# clapclap1386.net
KiCad netlist of a schematic drawn in EAGLE
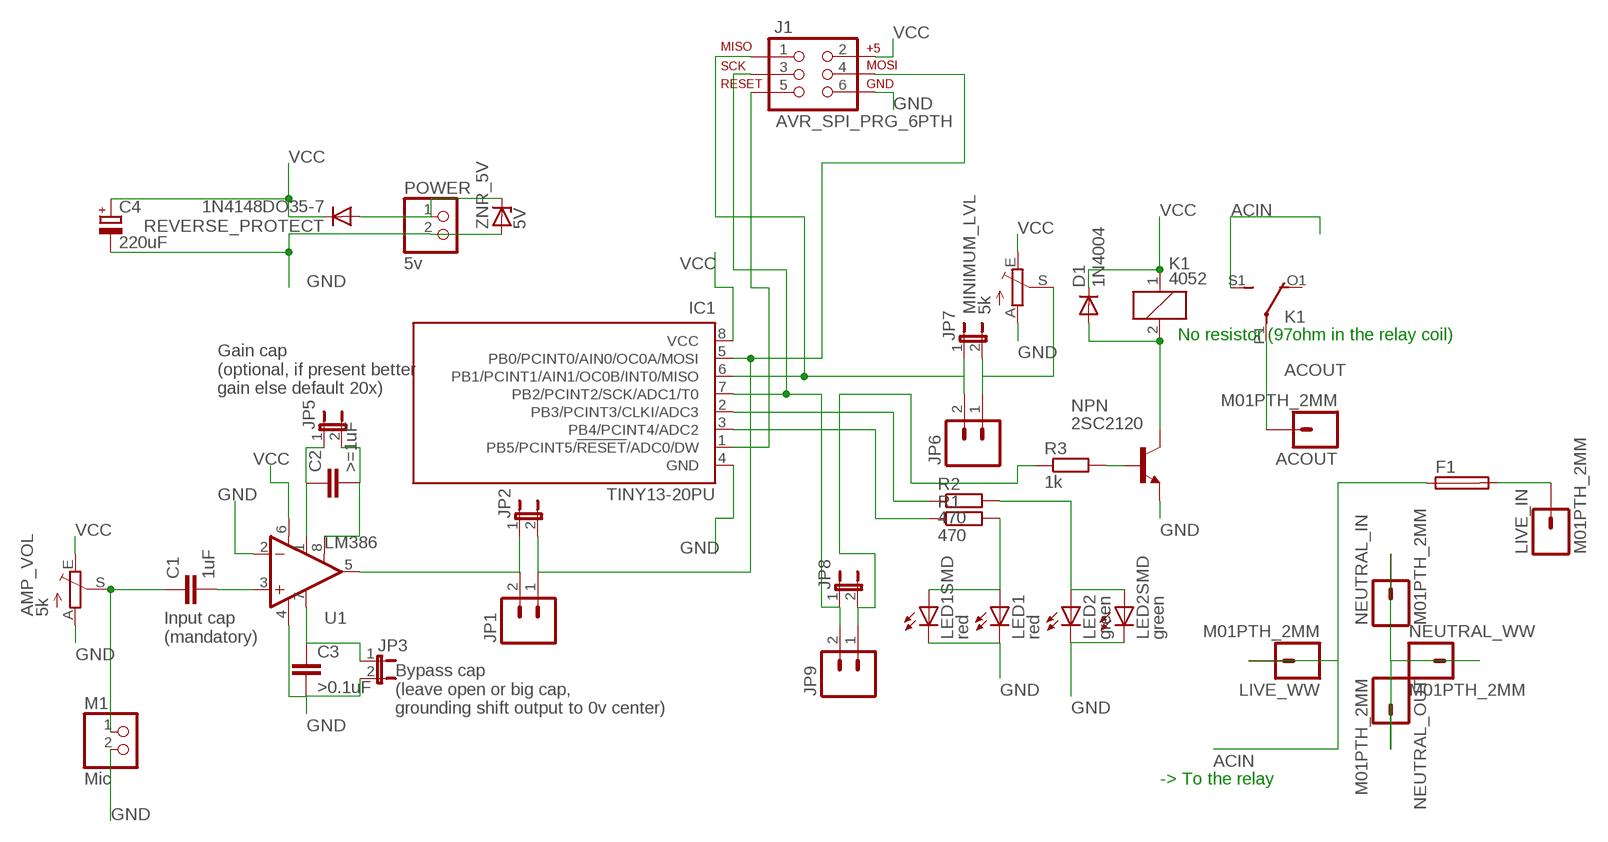
[diagram p0: schematic, sheet 1]

(export (version "E")
  (design (tool "Eeschema 10.0.6"))
  (components
    (comp (ref "ACOUT")
      (value "M01PTH_2MM")
      (footprint "eagle-import:1X01_2MM")
      (libsource (lib "eagle-import") (part "M01PTH_2MM"))
    )
    (comp (ref "AMP_VOL")
      (value "5k")
      (footprint "eagle-import:CT6")
      (libsource (lib "eagle-import") (part "TRIM_EU-CT6"))
    )
    (comp (ref "C1")
      (value "1uF")
      (footprint "eagle-import:C050-024X044")
      (libsource (lib "eagle-import") (part "C-EU050-024X044"))
    )
    (comp (ref "C2")
      (value ">=1uF")
      (footprint "eagle-import:C050-024X044")
      (libsource (lib "eagle-import") (part "C-EU050-024X044"))
    )
    (comp (ref "C3")
      (value ">0.1uF")
      (footprint "eagle-import:C025-025X050")
      (libsource (lib "eagle-import") (part "C-EU025-025X050"))
    )
    (comp (ref "C4")
      (value "220uF")
      (footprint "eagle-import:E2,5-6E")
      (libsource (lib "eagle-import") (part "CPOL-EUE2,5-6E"))
    )
    (comp (ref "D1")
      (value "1N4004")
      (footprint "eagle-import:DO41-10")
      (libsource (lib "eagle-import") (part "1N4004"))
    )
    (comp (ref "F1")
      (value "TE5")
      (footprint "eagle-import:TE5")
      (libsource (lib "eagle-import") (part "TE5"))
    )
    (comp (ref "IC1")
      (value "TINY13-20PU")
      (footprint "eagle-import:DIL08")
      (fields (field (name "MPN") "ATTINY13-20PU"))
      (libsource (lib "eagle-import") (part "TINY13PU-20"))
    )
    (comp (ref "J1")
      (value "AVR_SPI_PRG_6PTH")
      (footprint "eagle-import:2X3")
      (libsource (lib "eagle-import") (part "AVR_SPI_PRG_6PTH"))
    )
    (comp (ref "JP1")
      (value "M02PTH")
      (footprint "eagle-import:1X02")
      (libsource (lib "eagle-import") (part "M02PTH"))
    )
    (comp (ref "JP2")
      (value "JUMPER-2SMD-NO")
      (footprint "eagle-import:SJ_2S-NO")
      (libsource (lib "eagle-import") (part "JUMPER-2SMD-NO"))
    )
    (comp (ref "JP3")
      (value "JUMPER-2SMD-NO")
      (footprint "eagle-import:SJ_2S-NO")
      (libsource (lib "eagle-import") (part "JUMPER-2SMD-NO"))
    )
    (comp (ref "JP5")
      (value "JUMPER-2SMD-NO")
      (footprint "eagle-import:SJ_2S-NO")
      (libsource (lib "eagle-import") (part "JUMPER-2SMD-NO"))
    )
    (comp (ref "JP6")
      (value "M02PTH")
      (footprint "eagle-import:1X02")
      (libsource (lib "eagle-import") (part "M02PTH"))
    )
    (comp (ref "JP7")
      (value "JUMPER-2SMD-NO")
      (footprint "eagle-import:SJ_2S-NO")
      (libsource (lib "eagle-import") (part "JUMPER-2SMD-NO"))
    )
    (comp (ref "JP8")
      (value "JUMPER-2SMD-NO")
      (footprint "eagle-import:SJ_2S-NO")
      (libsource (lib "eagle-import") (part "JUMPER-2SMD-NO"))
    )
    (comp (ref "JP9")
      (value "M02PTH")
      (footprint "eagle-import:1X02")
      (libsource (lib "eagle-import") (part "M02PTH"))
    )
    (comp (ref "K1")
      (value "4052")
      (footprint "eagle-import:F4052")
      (libsource (lib "eagle-import") (part "4052"))
    )
    (comp (ref "LED1")
      (value "red")
      (footprint "eagle-import:LED3MM")
      (libsource (lib "eagle-import") (part "LED3MM"))
    )
    (comp (ref "LED1SMD")
      (value "red")
      (footprint "eagle-import:KA-3528ASYC")
      (libsource (lib "eagle-import") (part "LEDKA-3528ASYC"))
    )
    (comp (ref "LED2")
      (value "green")
      (footprint "eagle-import:LED3MM")
      (libsource (lib "eagle-import") (part "LED3MM"))
    )
    (comp (ref "LED2SMD")
      (value "green")
      (footprint "eagle-import:KA-3528ASYC")
      (libsource (lib "eagle-import") (part "LEDKA-3528ASYC"))
    )
    (comp (ref "LIVE_IN")
      (value "M01PTH_2MM")
      (footprint "eagle-import:1X01_2MM")
      (libsource (lib "eagle-import") (part "M01PTH_2MM"))
    )
    (comp (ref "LIVE_WW")
      (value "M01PTH_2MM")
      (footprint "eagle-import:1X01_2MM")
      (libsource (lib "eagle-import") (part "M01PTH_2MM"))
    )
    (comp (ref "M1")
      (value "Mic")
      (footprint "eagle-import:1X02")
      (libsource (lib "eagle-import") (part "PINHD-1X2"))
    )
    (comp (ref "MINIMUM_LVL")
      (value "5k")
      (footprint "eagle-import:CT6")
      (libsource (lib "eagle-import") (part "TRIM_EU-CT6"))
    )
    (comp (ref "NEUTRAL_IN")
      (value "M01PTH_2MM")
      (footprint "eagle-import:1X01_2MM")
      (libsource (lib "eagle-import") (part "M01PTH_2MM"))
    )
    (comp (ref "NEUTRAL_OUT")
      (value "M01PTH_2MM")
      (footprint "eagle-import:1X01_2MM")
      (libsource (lib "eagle-import") (part "M01PTH_2MM"))
    )
    (comp (ref "NEUTRAL_WW")
      (value "M01PTH_2MM")
      (footprint "eagle-import:1X01_2MM")
      (libsource (lib "eagle-import") (part "M01PTH_2MM"))
    )
    (comp (ref "NPN")
      (value "2SC2120")
      (footprint "eagle-import:TO92-ECB")
      (libsource (lib "eagle-import") (part "-NPN-TO92-ECB"))
    )
    (comp (ref "POWER")
      (value "5v")
      (footprint "eagle-import:1X02")
      (libsource (lib "eagle-import") (part "PINHD-1X2"))
    )
    (comp (ref "R1")
      (value "470")
      (footprint "eagle-import:0204V")
      (libsource (lib "eagle-import") (part "R-EU_0204/2V"))
    )
    (comp (ref "R2")
      (value "470")
      (footprint "eagle-import:0204V")
      (libsource (lib "eagle-import") (part "R-EU_0204/2V"))
    )
    (comp (ref "R3")
      (value "1k")
      (footprint "eagle-import:0207_2V")
      (libsource (lib "eagle-import") (part "R-EU_0207/2V"))
    )
    (comp (ref "REVERSE_PROTECT")
      (value "1N4148DO35-7")
      (footprint "eagle-import:DO35-7")
      (libsource (lib "eagle-import") (part "1N4148DO35-7"))
    )
    (comp (ref "U1")
      (value "LM386")
      (footprint "eagle-import:DIP08")
      (libsource (lib "eagle-import") (part "LM386"))
    )
    (comp (ref "ZNR_5V")
      (value "5V")
      (footprint "eagle-import:ZDIO-2.5")
      (libsource (lib "eagle-import") (part "ZENER-DIODEZD-2.5"))
    )
  )
  (nets
    (net (code "1") (name "/ACIN") (class "Default")
      (node (ref "F1") (pin "1") (pinfunction "1_1") (pintype "passive"))
      (node (ref "K1") (pin "S1") (pinfunction "S_S1") (pintype "passive"))
      (node (ref "LIVE_WW") (pin "1") (pinfunction "1_1") (pintype "passive"))
    )
    (net (code "2") (name "/ACOUT") (class "Default")
      (node (ref "ACOUT") (pin "1") (pinfunction "1_1") (pintype "passive"))
      (node (ref "K1") (pin "P1") (pinfunction "P_P1") (pintype "passive"))
    )
    (net (code "3") (name "/GND") (class "Default")
      (node (ref "AMP_VOL") (pin "A") (pinfunction "A_A") (pintype "passive"))
      (node (ref "C3") (pin "2") (pinfunction "2_2") (pintype "passive"))
      (node (ref "C4") (pin "-") (pinfunction "-_-") (pintype "passive"))
      (node (ref "IC1") (pin "4") (pinfunction "GND_4") (pintype "power_in"))
      (node (ref "J1") (pin "6") (pinfunction "6_6") (pintype "passive"))
      (node (ref "JP3") (pin "2") (pinfunction "2_2") (pintype "passive"))
      (node (ref "LED1") (pin "K") (pinfunction "C_K") (pintype "passive"))
      (node (ref "LED1SMD") (pin "C") (pinfunction "C_C") (pintype "passive"))
      (node (ref "LED2") (pin "K") (pinfunction "C_K") (pintype "passive"))
      (node (ref "LED2SMD") (pin "C") (pinfunction "C_C") (pintype "passive"))
      (node (ref "M1") (pin "2") (pinfunction "2_2") (pintype "passive"))
      (node (ref "MINIMUM_LVL") (pin "A") (pinfunction "A_A") (pintype "passive"))
      (node (ref "NPN") (pin "E") (pinfunction "E_E") (pintype "passive"))
      (node (ref "POWER") (pin "2") (pinfunction "2_2") (pintype "passive"))
      (node (ref "U1") (pin "2") (pinfunction "-IN_2") (pintype "input"))
      (node (ref "U1") (pin "4") (pinfunction "V-_4") (pintype "power_in"))
      (node (ref "ZNR_5V") (pin "A") (pinfunction "A_A") (pintype "passive"))
    )
    (net (code "4") (name "/VCC") (class "Default")
      (node (ref "AMP_VOL") (pin "E") (pinfunction "E_E") (pintype "passive"))
      (node (ref "C4") (pin "+") (pinfunction "+_+") (pintype "passive"))
      (node (ref "D1") (pin "C") (pinfunction "C_C") (pintype "passive"))
      (node (ref "IC1") (pin "8") (pinfunction "VCC_8") (pintype "power_in"))
      (node (ref "J1") (pin "2") (pinfunction "2_2") (pintype "passive"))
      (node (ref "K1") (pin "1") (pinfunction "1_1") (pintype "passive"))
      (node (ref "MINIMUM_LVL") (pin "E") (pinfunction "E_E") (pintype "passive"))
      (node (ref "REVERSE_PROTECT") (pin "C") (pinfunction "C_C") (pintype "passive"))
      (node (ref "U1") (pin "6") (pinfunction "V+_6") (pintype "power_in"))
    )
    (net (code "5") (name "Net-(AMP_VOL-PadS)") (class "Default")
      (node (ref "AMP_VOL") (pin "S") (pinfunction "S_S") (pintype "passive"))
      (node (ref "C1") (pin "1") (pinfunction "1_1") (pintype "passive"))
      (node (ref "M1") (pin "1") (pinfunction "1_1") (pintype "passive"))
    )
    (net (code "6") (name "Net-(C2-Pad1)") (class "Default")
      (node (ref "C2") (pin "1") (pinfunction "1_1") (pintype "passive"))
      (node (ref "JP5") (pin "1") (pinfunction "1_1") (pintype "passive"))
      (node (ref "U1") (pin "1") (pinfunction "GAIN_1") (pintype "bidirectional"))
    )
    (net (code "7") (name "Net-(C2-Pad2)") (class "Default")
      (node (ref "C2") (pin "2") (pinfunction "2_2") (pintype "passive"))
      (node (ref "JP5") (pin "2") (pinfunction "2_2") (pintype "passive"))
      (node (ref "U1") (pin "8") (pinfunction "GAIN_8") (pintype "bidirectional"))
    )
    (net (code "8") (name "Net-(D1-PadA)") (class "Default")
      (node (ref "D1") (pin "A") (pinfunction "A_A") (pintype "passive"))
      (node (ref "K1") (pin "2") (pinfunction "2_2") (pintype "passive"))
      (node (ref "NPN") (pin "C") (pinfunction "C_C") (pintype "passive"))
    )
    (net (code "9") (name "Net-(F1-Pad2)") (class "Default")
      (node (ref "F1") (pin "2") (pinfunction "2_2") (pintype "passive"))
      (node (ref "LIVE_IN") (pin "1") (pinfunction "1_1") (pintype "passive"))
    )
    (net (code "10") (name "Net-(IC1-PB0{slash}PCINT0{slash}AIN0{slash}OC0A{slash}MOSI)") (class "Default")
      (node (ref "IC1") (pin "5") (pinfunction "PB0/PCINT0/AIN0/OC0A/MOSI_5") (pintype "bidirectional"))
      (node (ref "J1") (pin "4") (pinfunction "4_4") (pintype "passive"))
      (node (ref "JP1") (pin "1") (pinfunction "1_1") (pintype "passive"))
      (node (ref "JP2") (pin "2") (pinfunction "2_2") (pintype "passive"))
    )
    (net (code "11") (name "Net-(IC1-PB1{slash}PCINT1{slash}AIN1{slash}OC0B{slash}INT0{slash}MISO)") (class "Default")
      (node (ref "IC1") (pin "6") (pinfunction "PB1/PCINT1/AIN1/OC0B/INT0/MISO_6") (pintype "bidirectional"))
      (node (ref "J1") (pin "1") (pinfunction "1_1") (pintype "passive"))
      (node (ref "JP6") (pin "2") (pinfunction "2_2") (pintype "passive"))
      (node (ref "JP7") (pin "1") (pinfunction "1_1") (pintype "passive"))
    )
    (net (code "12") (name "Net-(IC1-PB2{slash}PCINT2{slash}SCK{slash}ADC1{slash}T0)") (class "Default")
      (node (ref "IC1") (pin "7") (pinfunction "PB2/PCINT2/SCK/ADC1/T0_7") (pintype "bidirectional"))
      (node (ref "J1") (pin "3") (pinfunction "3_3") (pintype "passive"))
      (node (ref "JP8") (pin "1") (pinfunction "1_1") (pintype "passive"))
      (node (ref "JP9") (pin "2") (pinfunction "2_2") (pintype "passive"))
    )
    (net (code "13") (name "Net-(IC1-PB3{slash}PCINT3{slash}CLKI{slash}ADC3)") (class "Default")
      (node (ref "IC1") (pin "2") (pinfunction "PB3/PCINT3/CLKI/ADC3_2") (pintype "bidirectional"))
      (node (ref "R2") (pin "1") (pinfunction "1_1") (pintype "passive"))
    )
    (net (code "14") (name "Net-(IC1-PB4{slash}PCINT4{slash}ADC2)") (class "Default")
      (node (ref "IC1") (pin "3") (pinfunction "PB4/PCINT4/ADC2_3") (pintype "bidirectional"))
      (node (ref "R1") (pin "1") (pinfunction "1_1") (pintype "passive"))
    )
    (net (code "15") (name "Net-(IC1-PB5{slash}PCINT5{slash}~{RESET}{slash}ADC0{slash}DW)") (class "Default")
      (node (ref "IC1") (pin "1") (pinfunction "PB5/PCINT5/~{RESET}/ADC0/DW_1") (pintype "bidirectional"))
      (node (ref "J1") (pin "5") (pinfunction "5_5") (pintype "passive"))
    )
    (net (code "16") (name "Net-(JP6-Pad1)") (class "Default")
      (node (ref "JP6") (pin "1") (pinfunction "1_1") (pintype "passive"))
      (node (ref "JP7") (pin "2") (pinfunction "2_2") (pintype "passive"))
      (node (ref "MINIMUM_LVL") (pin "S") (pinfunction "S_S") (pintype "passive"))
    )
    (net (code "17") (name "Net-(JP8-Pad2)") (class "Default")
      (node (ref "JP8") (pin "2") (pinfunction "2_2") (pintype "passive"))
      (node (ref "JP9") (pin "1") (pinfunction "1_1") (pintype "passive"))
      (node (ref "R3") (pin "1") (pinfunction "1_1") (pintype "passive"))
    )
    (net (code "18") (name "Net-(LED1-PadA)") (class "Default")
      (node (ref "LED1") (pin "A") (pinfunction "A_A") (pintype "passive"))
      (node (ref "LED1SMD") (pin "A") (pinfunction "A_A") (pintype "passive"))
      (node (ref "R1") (pin "2") (pinfunction "2_2") (pintype "passive"))
    )
    (net (code "19") (name "Net-(LED2-PadA)") (class "Default")
      (node (ref "LED2") (pin "A") (pinfunction "A_A") (pintype "passive"))
      (node (ref "LED2SMD") (pin "A") (pinfunction "A_A") (pintype "passive"))
      (node (ref "R2") (pin "2") (pinfunction "2_2") (pintype "passive"))
    )
    (net (code "20") (name "Net-(NEUTRAL_IN-Pad1)") (class "Default")
      (node (ref "NEUTRAL_IN") (pin "1") (pinfunction "1_1") (pintype "passive"))
      (node (ref "NEUTRAL_OUT") (pin "1") (pinfunction "1_1") (pintype "passive"))
      (node (ref "NEUTRAL_WW") (pin "1") (pinfunction "1_1") (pintype "passive"))
    )
    (net (code "21") (name "Net-(NPN-PadB)") (class "Default")
      (node (ref "NPN") (pin "B") (pinfunction "B_B") (pintype "passive"))
      (node (ref "R3") (pin "2") (pinfunction "2_2") (pintype "passive"))
    )
    (net (code "22") (name "Net-(POWER-Pad1)") (class "Default")
      (node (ref "POWER") (pin "1") (pinfunction "1_1") (pintype "passive"))
      (node (ref "REVERSE_PROTECT") (pin "A") (pinfunction "A_A") (pintype "passive"))
      (node (ref "ZNR_5V") (pin "C") (pinfunction "C_C") (pintype "passive"))
    )
    (net (code "23") (name "Net-(U1-+IN)") (class "Default")
      (node (ref "C1") (pin "2") (pinfunction "2_2") (pintype "passive"))
      (node (ref "U1") (pin "3") (pinfunction "+IN_3") (pintype "input"))
    )
    (net (code "24") (name "Net-(U1-BP)") (class "Default")
      (node (ref "C3") (pin "1") (pinfunction "1_1") (pintype "passive"))
      (node (ref "JP3") (pin "1") (pinfunction "1_1") (pintype "passive"))
      (node (ref "U1") (pin "7") (pinfunction "BP_7") (pintype "bidirectional"))
    )
    (net (code "25") (name "Net-(U1-OUT)") (class "Default")
      (node (ref "JP1") (pin "2") (pinfunction "2_2") (pintype "passive"))
      (node (ref "JP2") (pin "1") (pinfunction "1_1") (pintype "passive"))
      (node (ref "U1") (pin "5") (pinfunction "OUT_5") (pintype "output"))
    )
    (net (code "26") (name "unconnected-(K1B-O-PadO1)") (class "Default")
      (node (ref "K1") (pin "O1") (pinfunction "O_O1") (pintype "passive"))
    )
  )
)
